# Bank_0_Bank_14.net
KiCad netlist of a schematic drawn in Altium Designer
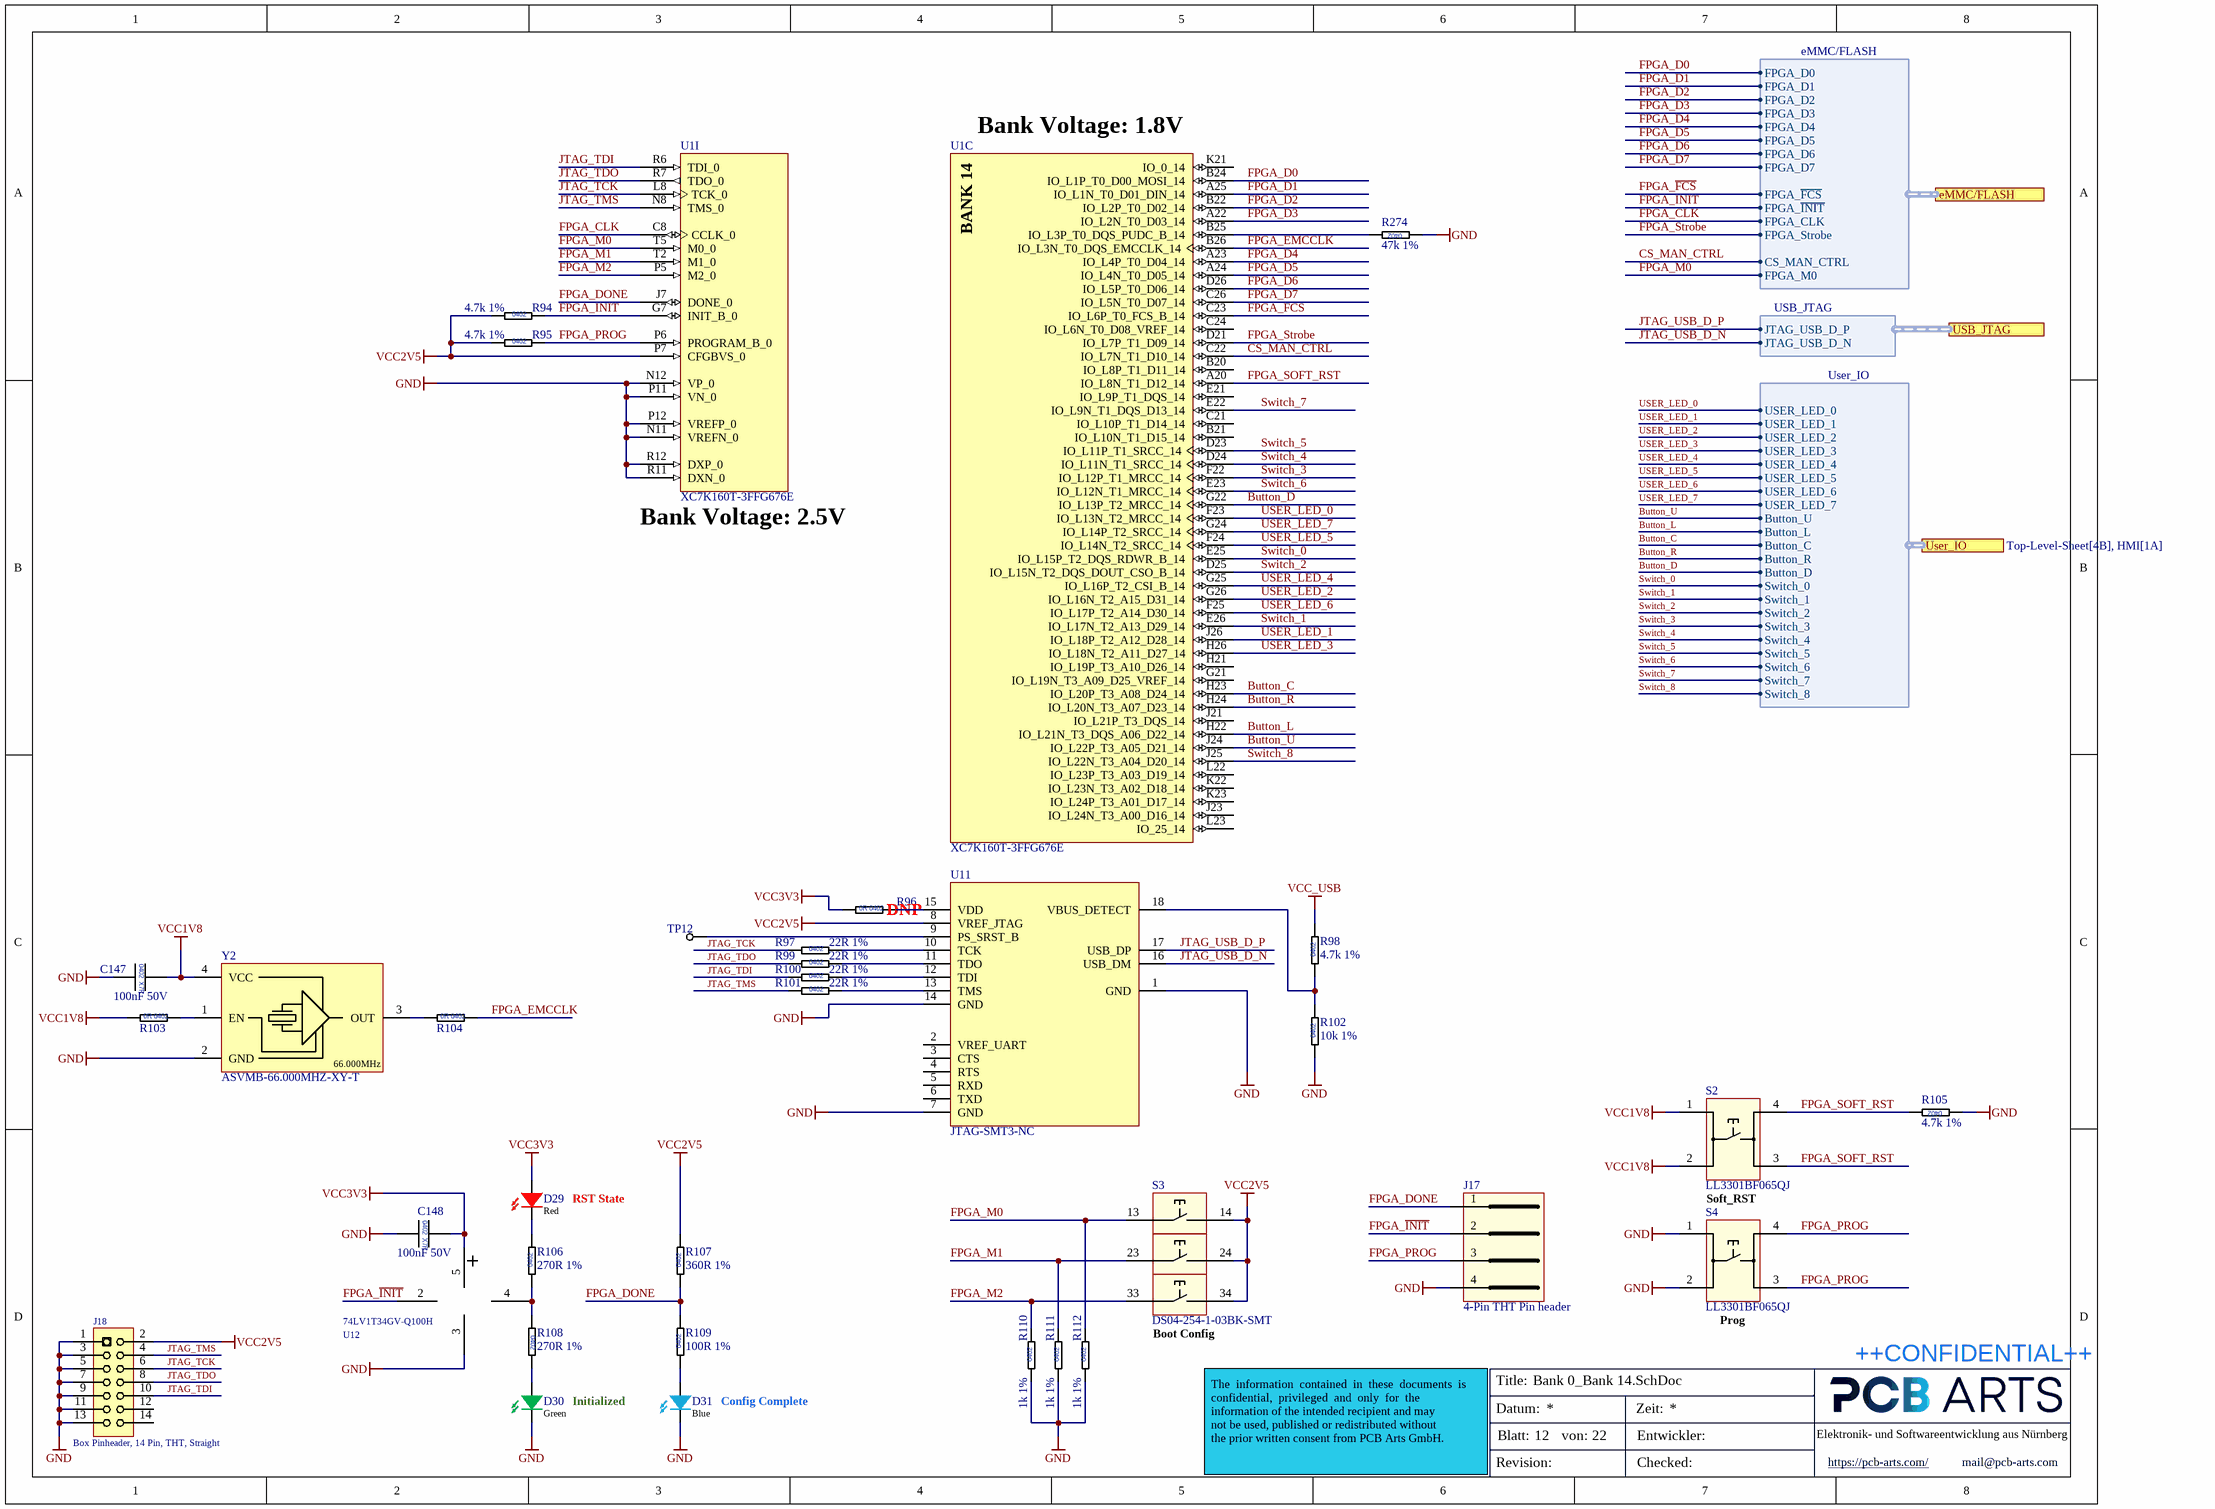
[diagram p0: Bank 0_Bank 14.SchDoc]

(export (version "E")
  (design (tool "Eeschema 10.0.6"))
  (components
    (comp (ref "C147")
      (value "100nF 50V")
      (footprint "Cap:CAP_0402_L")
      (description "Multilayer Ceramic Capacitors MLCC - SMD/SMT 0402 50VDC")
      (libsource (lib "Cap") (part "CAP_0402_100nF_50V"))
    )
    (comp (ref "C148")
      (value "100nF 50V")
      (footprint "Cap:CAP_0402_L")
      (description "Multilayer Ceramic Capacitors MLCC - SMD/SMT 0402 50VDC")
      (libsource (lib "Cap") (part "CAP_0402_100nF_50V"))
    )
    (comp (ref "D29")
      (value "LTST-S270KRKT")
      (footprint "Active:LED-0603 Sideview")
      (description "RED  0603 Light Emitting Diode")
      (fields (field (name "COLOR") "Red"))
      (libsource (lib "Active") (part "LED 0603 Red Sideview"))
    )
    (comp (ref "D30")
      (value "LTST-S270KGKT")
      (footprint "Active:LED-0603 Sideview")
      (description "GREEN  0603 Light Emitting Diode")
      (fields (field (name "COLOR") "Green"))
      (libsource (lib "Active") (part "LED 0603 Green Sideview"))
    )
    (comp (ref "D31")
      (value "LTST-S270TBKT")
      (footprint "Active:LED-0603 Sideview")
      (description "BLUE  0603 Light Emitting Diode")
      (fields (field (name "COLOR") "Blue"))
      (libsource (lib "Active") (part "LED 0603 Blue Sideview"))
    )
    (comp (ref "J17")
      (value "4-Pin THT Pin header")
      (footprint "Conn:61300411121")
      (description "WR-PHD 2.54mm 4Pin THT Header")
      (libsource (lib "Conn") (part "61300411121_WR-PHD 2.54mm 4Pin THT Header"))
    )
    (comp (ref "J18")
      (value "Box Pinheader, 14 Pin, THT, Straight")
      (footprint "Conn:87832-1420")
      (description "Box Pin header THT 2.00mm 14Pol Straight")
      (libsource (lib "Conn") (part "87832-1420_Box Pin header THT 2.00mm Box 14Pol Straight"))
    )
    (comp (ref "R94")
      (value "4.7k 1%")
      (footprint "Res:RES_0402_L")
      (description "Thick Film Resistors - SMD 4.7kOhm 1%")
      (libsource (lib "Res") (part "RES_0402_4.7k_1%"))
    )
    (comp (ref "R95")
      (value "4.7k 1%")
      (footprint "Res:RES_0402_L")
      (description "Thick Film Resistors - SMD 4.7kOhm 1%")
      (libsource (lib "Res") (part "RES_0402_4.7k_1%"))
    )
    (comp (ref "R96")
      (value "0R Jumper")
      (footprint "Res:RES_0402_L")
      (description "Thick Film Resistors - SMD 0Ohm")
      (libsource (lib "Res") (part "RES_0402_0R Jumper"))
    )
    (comp (ref "R97")
      (value "22R 1%")
      (footprint "Res:RES_0402_L")
      (description "Thick Film Resistors - SMD 22Ohm 1%")
      (libsource (lib "Res") (part "RES_0402_22R_1%"))
    )
    (comp (ref "R98")
      (value "4.7k 1%")
      (footprint "Res:RES_0402_L")
      (description "Thick Film Resistors - SMD 4.7kOhm 1%")
      (libsource (lib "Res") (part "RES_0402_4.7k_1%"))
    )
    (comp (ref "R99")
      (value "22R 1%")
      (footprint "Res:RES_0402_L")
      (description "Thick Film Resistors - SMD 22Ohm 1%")
      (libsource (lib "Res") (part "RES_0402_22R_1%"))
    )
    (comp (ref "R100")
      (value "22R 1%")
      (footprint "Res:RES_0402_L")
      (description "Thick Film Resistors - SMD 22Ohm 1%")
      (libsource (lib "Res") (part "RES_0402_22R_1%"))
    )
    (comp (ref "R101")
      (value "22R 1%")
      (footprint "Res:RES_0402_L")
      (description "Thick Film Resistors - SMD 22Ohm 1%")
      (libsource (lib "Res") (part "RES_0402_22R_1%"))
    )
    (comp (ref "R102")
      (value "10k 1%")
      (footprint "Res:RES_0402_L")
      (description "Thick Film Resistors - SMD 10kOhm 1%")
      (libsource (lib "Res") (part "RES_0402_10k_1%"))
    )
    (comp (ref "R103")
      (value "0R Jumper")
      (footprint "Res:RES_0402_L")
      (description "Thick Film Resistors - SMD 0Ohm")
      (libsource (lib "Res") (part "RES_0402_0R Jumper"))
    )
    (comp (ref "R104")
      (value "0R Jumper")
      (footprint "Res:RES_0402_L")
      (description "Thick Film Resistors - SMD 0Ohm")
      (libsource (lib "Res") (part "RES_0402_0R Jumper"))
    )
    (comp (ref "R105")
      (value "4.7k 1%")
      (footprint "Res:RES_0402_L")
      (description "Thick Film Resistors - SMD 4.7kOhm 1%")
      (libsource (lib "Res") (part "RES_0402_4.7k_1%"))
    )
    (comp (ref "R106")
      (value "270R 1%")
      (footprint "Res:RES_0402_L")
      (description "Thick Film Resistors - SMD 270Ohm 1%")
      (libsource (lib "Res") (part "RES_0402_270R 1%"))
    )
    (comp (ref "R107")
      (value "360R 1%")
      (footprint "Res:RES_0402_L")
      (description "Thick Film Resistors - SMD 360Ohm 1%")
      (libsource (lib "Res") (part "RES_0402_360R_1%"))
    )
    (comp (ref "R108")
      (value "270R 1%")
      (footprint "Res:RES_0402_L")
      (description "Thick Film Resistors - SMD 270Ohm 1%")
      (libsource (lib "Res") (part "RES_0402_270R 1%"))
    )
    (comp (ref "R109")
      (value "100R 1%")
      (footprint "Res:RES_0402_L")
      (description "Thick Film Resistors - SMD 100Ohm 1%")
      (libsource (lib "Res") (part "RES_0402_100R_1%"))
    )
    (comp (ref "R110")
      (value "1k 1%")
      (footprint "Res:RES_0402_L")
      (description "Thick Film Resistors - SMD 1kOhm 1%")
      (libsource (lib "Res") (part "RES_0402_1k_1%"))
    )
    (comp (ref "R111")
      (value "1k 1%")
      (footprint "Res:RES_0402_L")
      (description "Thick Film Resistors - SMD 1kOhm 1%")
      (libsource (lib "Res") (part "RES_0402_1k_1%"))
    )
    (comp (ref "R112")
      (value "1k 1%")
      (footprint "Res:RES_0402_L")
      (description "Thick Film Resistors - SMD 1kOhm 1%")
      (libsource (lib "Res") (part "RES_0402_1k_1%"))
    )
    (comp (ref "R274")
      (value "47k 1%")
      (footprint "Res:RES_0402_L")
      (description "Thick Film Resistors - SMD 47kOhm 1%")
      (libsource (lib "Res") (part "RES_0402_47k_1%"))
    )
    (comp (ref "S2")
      (value "LL3301BF065QJ")
      (footprint "Electro_Mech:LL3301BF065QJ")
      (description "SPST Top Actuated  Button, 65gf, SMD h: 9.8mm")
      (libsource (lib "Electro_Mech") (part "LL3301BF065QJ_SPST Top Actuated  Button, 65gf, SMD h{colon} 9.8mm"))
    )
    (comp (ref "S3")
      (value "DS04-254-1-03BK-SMT")
      (footprint "Electro_Mech:CUI DS04-254-SMT Series, 3 Pole")
      (description "SMD DIP Switch, 3 Pos, Slide actuator")
      (libsource (lib "Electro_Mech") (part "DS04-254-1-03BK-SMT"))
    )
    (comp (ref "S4")
      (value "LL3301BF065QJ")
      (footprint "Electro_Mech:LL3301BF065QJ")
      (description "SPST Top Actuated  Button, 65gf, SMD h: 9.8mm")
      (libsource (lib "Electro_Mech") (part "LL3301BF065QJ_SPST Top Actuated  Button, 65gf, SMD h{colon} 9.8mm"))
    )
    (comp (ref "TP12")
      (value "Testpoint")
      (footprint "Electro_mech:Testpoint 0.8mm")
      (description "Testpoint 0.8mm")
      (libsource (lib "Electro_Mech") (part "Testpoint 0.8mm"))
    )
    (comp (ref "U1")
      (value "XC7K160T-3FFG676E")
      (footprint "Digital:BGA100P2700X2700X317-676N")
      (description "Kintex-7 FPGA, 400 User I/Os, 8 GTX, 676-Ball BGA, Speed Grade 3, Extended Grade, Pb-Free")
      (libsource (lib "Digital") (part "XC7K160T-3FFG676E_Kintex-7 FPGA, 400 User I/Os, 8 GTX, FFG676"))
    )
    (comp (ref "U11")
      (value "JTAG-SMT3-NC")
      (footprint "Conn_Modules:JTAG-SMT3-NC")
      (description "Surface-mount JTAG Programming + UART Module")
      (libsource (lib "Conn_Modules") (part "JTAG-SMT3-NC_Surface-mount JTAG Programming + UART Module"))
    )
    (comp (ref "U12")
      (value "74LV1T34GV-Q100H")
      (footprint "Digital:SOT95P275X110-5N")
      (description "Single supply translating buffer")
      (libsource (lib "Digital") (part "74LV1T34GV-Q100H_Single supply translating buffe"))
    )
    (comp (ref "Y2")
      (value "ASVMB-66.000MHZ-XY-T")
      (footprint "Timer:ASVMB Series")
      (description "Clock-Memsoszillator 66.000MHz 1.8V 10ppm -40C +105C")
      (libsource (lib "Timer") (part "ASVMB-66.000MHZ-XY-T_Clock-Memsoszillator 66.000MHz 1.8V 10ppm -40C +105C"))
    )
  )
  (nets
    (net (code "4") (name "/Button_C") (class "Default")
      (node (ref "U1") (pin "H23") (pinfunction "IO_L20P_T3_A08_D24_14_H23") (pintype "bidirectional"))
    )
    (net (code "5") (name "/Button_D") (class "Default")
      (node (ref "U1") (pin "G22") (pinfunction "IO_L13P_T2_MRCC_14_G22") (pintype "bidirectional"))
    )
    (net (code "6") (name "/Button_L") (class "Default")
      (node (ref "U1") (pin "H22") (pinfunction "IO_L21N_T3_DQS_A06_D22_14_H22") (pintype "bidirectional"))
    )
    (net (code "7") (name "/Button_R") (class "Default")
      (node (ref "U1") (pin "H24") (pinfunction "IO_L20N_T3_A07_D23_14_H24") (pintype "bidirectional"))
    )
    (net (code "8") (name "/Button_U") (class "Default")
      (node (ref "U1") (pin "J24") (pinfunction "IO_L22P_T3_A05_D21_14_J24") (pintype "bidirectional"))
    )
    (net (code "9") (name "/CS_MAN_CTRL") (class "Default")
      (node (ref "U1") (pin "C22") (pinfunction "IO_L7N_T1_D10_14_C22") (pintype "bidirectional"))
    )
    (net (code "10") (name "/FPGA_CLK") (class "Default")
      (node (ref "U1") (pin "C8") (pinfunction "CCLK_0_C8") (pintype "bidirectional"))
    )
    (net (code "11") (name "/FPGA_D0") (class "Default")
      (node (ref "U1") (pin "B24") (pinfunction "IO_L1P_T0_D00_MOSI_14_B24") (pintype "bidirectional"))
    )
    (net (code "12") (name "/FPGA_D1") (class "Default")
      (node (ref "U1") (pin "A25") (pinfunction "IO_L1N_T0_D01_DIN_14_A25") (pintype "bidirectional"))
    )
    (net (code "13") (name "/FPGA_D2") (class "Default")
      (node (ref "U1") (pin "B22") (pinfunction "IO_L2P_T0_D02_14_B22") (pintype "bidirectional"))
    )
    (net (code "14") (name "/FPGA_D3") (class "Default")
      (node (ref "U1") (pin "A22") (pinfunction "IO_L2N_T0_D03_14_A22") (pintype "bidirectional"))
    )
    (net (code "15") (name "/FPGA_D4") (class "Default")
      (node (ref "U1") (pin "A23") (pinfunction "IO_L4P_T0_D04_14_A23") (pintype "bidirectional"))
    )
    (net (code "16") (name "/FPGA_D5") (class "Default")
      (node (ref "U1") (pin "A24") (pinfunction "IO_L4N_T0_D05_14_A24") (pintype "bidirectional"))
    )
    (net (code "17") (name "/FPGA_D6") (class "Default")
      (node (ref "U1") (pin "D26") (pinfunction "IO_L5P_T0_D06_14_D26") (pintype "bidirectional"))
    )
    (net (code "18") (name "/FPGA_D7") (class "Default")
      (node (ref "U1") (pin "C26") (pinfunction "IO_L5N_T0_D07_14_C26") (pintype "bidirectional"))
    )
    (net (code "19") (name "/FPGA_DONE") (class "Default")
      (node (ref "J17") (pin "1") (pinfunction "1_1") (pintype "passive"))
      (node (ref "R107") (pin "1") (pinfunction "1_1") (pintype "passive"))
      (node (ref "R109") (pin "2") (pinfunction "2_2") (pintype "passive"))
      (node (ref "U1") (pin "J7") (pinfunction "DONE_0_J7") (pintype "bidirectional"))
    )
    (net (code "20") (name "/FPGA_EMCCLK") (class "Default")
      (node (ref "R104") (pin "2") (pinfunction "2_2") (pintype "passive"))
      (node (ref "U1") (pin "B26") (pinfunction "IO_L3N_T0_DQS_EMCCLK_14_B26") (pintype "bidirectional"))
    )
    (net (code "21") (name "/FPGA_M0") (class "Default")
      (node (ref "R112") (pin "2") (pinfunction "2_2") (pintype "passive"))
      (node (ref "S3") (pin "13") (pinfunction "13_13") (pintype "passive"))
      (node (ref "U1") (pin "T5") (pinfunction "M0_0_T5") (pintype "input"))
    )
    (net (code "22") (name "/FPGA_M1") (class "Default")
      (node (ref "R111") (pin "2") (pinfunction "2_2") (pintype "passive"))
      (node (ref "S3") (pin "23") (pinfunction "23_23") (pintype "passive"))
      (node (ref "U1") (pin "T2") (pinfunction "M1_0_T2") (pintype "input"))
    )
    (net (code "23") (name "/FPGA_M2") (class "Default")
      (node (ref "R110") (pin "2") (pinfunction "2_2") (pintype "passive"))
      (node (ref "S3") (pin "33") (pinfunction "33_33") (pintype "passive"))
      (node (ref "U1") (pin "P5") (pinfunction "M2_0_P5") (pintype "input"))
    )
    (net (code "24") (name "/FPGA_PROG") (class "Default")
      (node (ref "J17") (pin "3") (pinfunction "3_3") (pintype "passive"))
      (node (ref "R95") (pin "2") (pinfunction "2_2") (pintype "passive"))
      (node (ref "S4") (pin "3") (pinfunction "3_3") (pintype "passive"))
      (node (ref "S4") (pin "4") (pinfunction "4_4") (pintype "passive"))
      (node (ref "U1") (pin "P6") (pinfunction "PROGRAM_B_0_P6") (pintype "input"))
    )
    (net (code "25") (name "/FPGA_SOFT_RST") (class "Default")
      (node (ref "R105") (pin "2") (pinfunction "2_2") (pintype "passive"))
      (node (ref "S2") (pin "3") (pinfunction "3_3") (pintype "passive"))
      (node (ref "S2") (pin "4") (pinfunction "4_4") (pintype "passive"))
      (node (ref "U1") (pin "A20") (pinfunction "IO_L8N_T1_D12_14_A20") (pintype "bidirectional"))
    )
    (net (code "26") (name "/FPGA_Strobe") (class "Default")
      (node (ref "U1") (pin "D21") (pinfunction "IO_L7P_T1_D09_14_D21") (pintype "bidirectional"))
    )
    (net (code "27") (name "/FPGA_~{FCS}") (class "Default")
      (node (ref "U1") (pin "C23") (pinfunction "IO_L6P_T0_FCS_B_14_C23") (pintype "bidirectional"))
    )
    (net (code "28") (name "/FPGA_~{INIT}") (class "Default")
      (node (ref "J17") (pin "2") (pinfunction "2_2") (pintype "passive"))
      (node (ref "R94") (pin "2") (pinfunction "2_2") (pintype "passive"))
      (node (ref "U1") (pin "G7") (pinfunction "INIT_B_0_G7") (pintype "bidirectional"))
      (node (ref "U12") (pin "2") (pinfunction "A_2") (pintype "passive"))
    )
    (net (code "29") (name "/JTAG_TCK") (class "Default")
      (node (ref "J18") (pin "6") (pinfunction "6_6") (pintype "passive"))
      (node (ref "R97") (pin "1") (pinfunction "1_1") (pintype "passive"))
      (node (ref "U1") (pin "L8") (pinfunction "TCK_0_L8") (pintype "input"))
    )
    (net (code "30") (name "/JTAG_TDI") (class "Default")
      (node (ref "J18") (pin "10") (pinfunction "10_10") (pintype "passive"))
      (node (ref "R100") (pin "1") (pinfunction "1_1") (pintype "passive"))
      (node (ref "U1") (pin "R6") (pinfunction "TDI_0_R6") (pintype "input"))
    )
    (net (code "31") (name "/JTAG_TDO") (class "Default")
      (node (ref "J18") (pin "8") (pinfunction "8_8") (pintype "passive"))
      (node (ref "R99") (pin "1") (pinfunction "1_1") (pintype "passive"))
      (node (ref "U1") (pin "R7") (pinfunction "TDO_0_R7") (pintype "output"))
    )
    (net (code "32") (name "/JTAG_TMS") (class "Default")
      (node (ref "J18") (pin "4") (pinfunction "4_4") (pintype "passive"))
      (node (ref "R101") (pin "1") (pinfunction "1_1") (pintype "passive"))
      (node (ref "U1") (pin "N8") (pinfunction "TMS_0_N8") (pintype "input"))
    )
    (net (code "33") (name "/JTAG_USB_D_N") (class "Default")
      (node (ref "U11") (pin "16") (pinfunction "USB_DM_16") (pintype "passive"))
    )
    (net (code "34") (name "/JTAG_USB_D_P") (class "Default")
      (node (ref "U11") (pin "17") (pinfunction "USB_DP_17") (pintype "passive"))
    )
    (net (code "35") (name "/Switch_0") (class "Default")
      (node (ref "U1") (pin "E25") (pinfunction "IO_L15P_T2_DQS_RDWR_B_14_E25") (pintype "bidirectional"))
    )
    (net (code "36") (name "/Switch_1") (class "Default")
      (node (ref "U1") (pin "E26") (pinfunction "IO_L17N_T2_A13_D29_14_E26") (pintype "bidirectional"))
    )
    (net (code "37") (name "/Switch_2") (class "Default")
      (node (ref "U1") (pin "D25") (pinfunction "IO_L15N_T2_DQS_DOUT_CSO_B_14_D25") (pintype "bidirectional"))
    )
    (net (code "38") (name "/Switch_3") (class "Default")
      (node (ref "U1") (pin "F22") (pinfunction "IO_L12P_T1_MRCC_14_F22") (pintype "bidirectional"))
    )
    (net (code "39") (name "/Switch_4") (class "Default")
      (node (ref "U1") (pin "D24") (pinfunction "IO_L11N_T1_SRCC_14_D24") (pintype "bidirectional"))
    )
    (net (code "40") (name "/Switch_5") (class "Default")
      (node (ref "U1") (pin "D23") (pinfunction "IO_L11P_T1_SRCC_14_D23") (pintype "bidirectional"))
    )
    (net (code "41") (name "/Switch_6") (class "Default")
      (node (ref "U1") (pin "E23") (pinfunction "IO_L12N_T1_MRCC_14_E23") (pintype "bidirectional"))
    )
    (net (code "42") (name "/Switch_7") (class "Default")
      (node (ref "U1") (pin "E22") (pinfunction "IO_L9N_T1_DQS_D13_14_E22") (pintype "bidirectional"))
    )
    (net (code "43") (name "/Switch_8") (class "Default")
      (node (ref "U1") (pin "J25") (pinfunction "IO_L22N_T3_A04_D20_14_J25") (pintype "bidirectional"))
    )
    (net (code "44") (name "/USER_LED_0") (class "Default")
      (node (ref "U1") (pin "F23") (pinfunction "IO_L13N_T2_MRCC_14_F23") (pintype "bidirectional"))
    )
    (net (code "45") (name "/USER_LED_1") (class "Default")
      (node (ref "U1") (pin "J26") (pinfunction "IO_L18P_T2_A12_D28_14_J26") (pintype "bidirectional"))
    )
    (net (code "46") (name "/USER_LED_2") (class "Default")
      (node (ref "U1") (pin "G26") (pinfunction "IO_L16N_T2_A15_D31_14_G26") (pintype "bidirectional"))
    )
    (net (code "47") (name "/USER_LED_3") (class "Default")
      (node (ref "U1") (pin "H26") (pinfunction "IO_L18N_T2_A11_D27_14_H26") (pintype "bidirectional"))
    )
    (net (code "48") (name "/USER_LED_4") (class "Default")
      (node (ref "U1") (pin "G25") (pinfunction "IO_L16P_T2_CSI_B_14_G25") (pintype "bidirectional"))
    )
    (net (code "49") (name "/USER_LED_5") (class "Default")
      (node (ref "U1") (pin "F24") (pinfunction "IO_L14N_T2_SRCC_14_F24") (pintype "bidirectional"))
    )
    (net (code "50") (name "/USER_LED_6") (class "Default")
      (node (ref "U1") (pin "F25") (pinfunction "IO_L17P_T2_A14_D30_14_F25") (pintype "bidirectional"))
    )
    (net (code "51") (name "/USER_LED_7") (class "Default")
      (node (ref "U1") (pin "G24") (pinfunction "IO_L14P_T2_SRCC_14_G24") (pintype "bidirectional"))
    )
    (net (code "55") (name "GND") (class "Default")
      (node (ref "C147") (pin "2") (pinfunction "2_2") (pintype "passive"))
      (node (ref "C148") (pin "2") (pinfunction "2_2") (pintype "passive"))
      (node (ref "D30") (pin "1") (pinfunction "1_1") (pintype "passive"))
      (node (ref "D31") (pin "1") (pinfunction "1_1") (pintype "passive"))
      (node (ref "J17") (pin "4") (pinfunction "4_4") (pintype "passive"))
      (node (ref "J18") (pin "1") (pinfunction "1_1") (pintype "passive"))
      (node (ref "J18") (pin "11") (pinfunction "11_11") (pintype "passive"))
      (node (ref "J18") (pin "13") (pinfunction "13_13") (pintype "passive"))
      (node (ref "J18") (pin "3") (pinfunction "3_3") (pintype "passive"))
      (node (ref "J18") (pin "5") (pinfunction "5_5") (pintype "passive"))
      (node (ref "J18") (pin "7") (pinfunction "7_7") (pintype "passive"))
      (node (ref "J18") (pin "9") (pinfunction "9_9") (pintype "passive"))
      (node (ref "R102") (pin "1") (pinfunction "1_1") (pintype "passive"))
      (node (ref "R105") (pin "1") (pinfunction "1_1") (pintype "passive"))
      (node (ref "R110") (pin "1") (pinfunction "1_1") (pintype "passive"))
      (node (ref "R111") (pin "1") (pinfunction "1_1") (pintype "passive"))
      (node (ref "R112") (pin "1") (pinfunction "1_1") (pintype "passive"))
      (node (ref "R274") (pin "1") (pinfunction "1_1") (pintype "passive"))
      (node (ref "S4") (pin "1") (pinfunction "1_1") (pintype "passive"))
      (node (ref "S4") (pin "2") (pinfunction "2_2") (pintype "passive"))
      (node (ref "U1") (pin "N11") (pinfunction "VREFN_0_N11") (pintype "input"))
      (node (ref "U1") (pin "N12") (pinfunction "VP_0_N12") (pintype "input"))
      (node (ref "U1") (pin "P11") (pinfunction "VN_0_P11") (pintype "input"))
      (node (ref "U1") (pin "P12") (pinfunction "VREFP_0_P12") (pintype "input"))
      (node (ref "U1") (pin "R11") (pinfunction "DXN_0_R11") (pintype "input"))
      (node (ref "U1") (pin "R12") (pinfunction "DXP_0_R12") (pintype "input"))
      (node (ref "U11") (pin "1") (pinfunction "GND_1") (pintype "passive"))
      (node (ref "U11") (pin "14") (pinfunction "GND_14") (pintype "passive"))
      (node (ref "U11") (pin "7") (pinfunction "GND_7") (pintype "passive"))
      (node (ref "U12") (pin "3") (pinfunction "GND_3") (pintype "passive"))
      (node (ref "Y2") (pin "2") (pinfunction "GND_2") (pintype "passive"))
    )
    (net (code "56") (name "Net-(D29-Pad1)") (class "Default")
      (node (ref "D29") (pin "1") (pinfunction "1_1") (pintype "passive"))
      (node (ref "R106") (pin "2") (pinfunction "2_2") (pintype "passive"))
    )
    (net (code "57") (name "Net-(D30-Pad2)") (class "Default")
      (node (ref "D30") (pin "2") (pinfunction "2_2") (pintype "passive"))
      (node (ref "R108") (pin "2") (pinfunction "2_2") (pintype "passive"))
    )
    (net (code "58") (name "Net-(D31-Pad2)") (class "Default")
      (node (ref "D31") (pin "2") (pinfunction "2_2") (pintype "passive"))
      (node (ref "R109") (pin "1") (pinfunction "1_1") (pintype "passive"))
    )
    (net (code "59") (name "Net-(TP12-GND)") (class "Default")
      (node (ref "TP12") (pin "1") (pinfunction "GND_1") (pintype "passive"))
      (node (ref "U11") (pin "9") (pinfunction "PS_SRST_B_9") (pintype "passive"))
    )
    (net (code "60") (name "Net-(U1C-IO_L3P_T0_DQS_PUDC_B_14)") (class "Default")
      (node (ref "R274") (pin "2") (pinfunction "2_2") (pintype "passive"))
      (node (ref "U1") (pin "B25") (pinfunction "IO_L3P_T0_DQS_PUDC_B_14_B25") (pintype "bidirectional"))
    )
    (net (code "61") (name "Net-(U11-TCK)") (class "Default")
      (node (ref "R97") (pin "2") (pinfunction "2_2") (pintype "passive"))
      (node (ref "U11") (pin "10") (pinfunction "TCK_10") (pintype "passive"))
    )
    (net (code "62") (name "Net-(U11-TDI)") (class "Default")
      (node (ref "R100") (pin "2") (pinfunction "2_2") (pintype "passive"))
      (node (ref "U11") (pin "12") (pinfunction "TDI_12") (pintype "passive"))
    )
    (net (code "63") (name "Net-(U11-TDO)") (class "Default")
      (node (ref "R99") (pin "2") (pinfunction "2_2") (pintype "passive"))
      (node (ref "U11") (pin "11") (pinfunction "TDO_11") (pintype "passive"))
    )
    (net (code "64") (name "Net-(U11-TMS)") (class "Default")
      (node (ref "R101") (pin "2") (pinfunction "2_2") (pintype "passive"))
      (node (ref "U11") (pin "13") (pinfunction "TMS_13") (pintype "passive"))
    )
    (net (code "65") (name "Net-(U11-VBUS_DETECT)") (class "Default")
      (node (ref "R102") (pin "2") (pinfunction "2_2") (pintype "passive"))
      (node (ref "R98") (pin "1") (pinfunction "1_1") (pintype "passive"))
      (node (ref "U11") (pin "18") (pinfunction "VBUS_DETECT_18") (pintype "passive"))
    )
    (net (code "66") (name "Net-(U11-VDD)") (class "Default")
      (node (ref "R96") (pin "2") (pinfunction "2_2") (pintype "passive"))
      (node (ref "U11") (pin "15") (pinfunction "VDD_15") (pintype "passive"))
    )
    (net (code "67") (name "Net-(U12-Y)") (class "Default")
      (node (ref "R106") (pin "1") (pinfunction "1_1") (pintype "passive"))
      (node (ref "R108") (pin "1") (pinfunction "1_1") (pintype "passive"))
      (node (ref "U12") (pin "4") (pinfunction "Y_4") (pintype "passive"))
    )
    (net (code "68") (name "Net-(Y2-EN)") (class "Default")
      (node (ref "R103") (pin "2") (pinfunction "2_2") (pintype "passive"))
      (node (ref "Y2") (pin "1") (pinfunction "EN_1") (pintype "passive"))
    )
    (net (code "69") (name "Net-(Y2-OUT)") (class "Default")
      (node (ref "R104") (pin "1") (pinfunction "1_1") (pintype "passive"))
      (node (ref "Y2") (pin "3") (pinfunction "OUT_3") (pintype "passive"))
    )
    (net (code "70") (name "VCC1V8") (class "Default")
      (node (ref "C147") (pin "1") (pinfunction "1_1") (pintype "passive"))
      (node (ref "R103") (pin "1") (pinfunction "1_1") (pintype "passive"))
      (node (ref "S2") (pin "1") (pinfunction "1_1") (pintype "passive"))
      (node (ref "S2") (pin "2") (pinfunction "2_2") (pintype "passive"))
      (node (ref "Y2") (pin "4") (pinfunction "VCC_4") (pintype "passive"))
    )
    (net (code "71") (name "VCC2V5") (class "Default")
      (node (ref "J18") (pin "2") (pinfunction "2_2") (pintype "passive"))
      (node (ref "R107") (pin "2") (pinfunction "2_2") (pintype "passive"))
      (node (ref "R94") (pin "1") (pinfunction "1_1") (pintype "passive"))
      (node (ref "R95") (pin "1") (pinfunction "1_1") (pintype "passive"))
      (node (ref "S3") (pin "14") (pinfunction "14_14") (pintype "passive"))
      (node (ref "S3") (pin "24") (pinfunction "24_24") (pintype "passive"))
      (node (ref "S3") (pin "34") (pinfunction "34_34") (pintype "passive"))
      (node (ref "U1") (pin "P7") (pinfunction "CFGBVS_0_P7") (pintype "input"))
      (node (ref "U11") (pin "8") (pinfunction "VREF_JTAG_8") (pintype "passive"))
    )
    (net (code "72") (name "VCC3V3") (class "Default")
      (node (ref "C148") (pin "1") (pinfunction "1_1") (pintype "passive"))
      (node (ref "D29") (pin "2") (pinfunction "2_2") (pintype "passive"))
      (node (ref "R96") (pin "1") (pinfunction "1_1") (pintype "passive"))
      (node (ref "U12") (pin "5") (pinfunction "VCC_5") (pintype "passive"))
    )
    (net (code "73") (name "VCC_USB") (class "Default")
      (node (ref "R98") (pin "2") (pinfunction "2_2") (pintype "passive"))
    )
    (net (code "74") (name "unconnected-(J18-Pad12)") (class "Default")
      (node (ref "J18") (pin "12") (pinfunction "12_12") (pintype "passive"))
    )
    (net (code "75") (name "unconnected-(J18-Pad14)") (class "Default")
      (node (ref "J18") (pin "14") (pinfunction "14_14") (pintype "passive"))
    )
    (net (code "76") (name "unconnected-(U1C-IO_0_14-PadK21)") (class "Default")
      (node (ref "U1") (pin "K21") (pinfunction "IO_0_14_K21") (pintype "bidirectional"))
    )
    (net (code "77") (name "unconnected-(U1C-IO_25_14-PadL23)") (class "Default")
      (node (ref "U1") (pin "L23") (pinfunction "IO_25_14_L23") (pintype "bidirectional"))
    )
    (net (code "78") (name "unconnected-(U1C-IO_L6N_T0_D08_VREF_14-PadC24)") (class "Default")
      (node (ref "U1") (pin "C24") (pinfunction "IO_L6N_T0_D08_VREF_14_C24") (pintype "bidirectional"))
    )
    (net (code "79") (name "unconnected-(U1C-IO_L8P_T1_D11_14-PadB20)") (class "Default")
      (node (ref "U1") (pin "B20") (pinfunction "IO_L8P_T1_D11_14_B20") (pintype "bidirectional"))
    )
    (net (code "80") (name "unconnected-(U1C-IO_L9P_T1_DQS_14-PadE21)") (class "Default")
      (node (ref "U1") (pin "E21") (pinfunction "IO_L9P_T1_DQS_14_E21") (pintype "bidirectional"))
    )
    (net (code "81") (name "unconnected-(U1C-IO_L10N_T1_D15_14-PadB21)") (class "Default")
      (node (ref "U1") (pin "B21") (pinfunction "IO_L10N_T1_D15_14_B21") (pintype "bidirectional"))
    )
    (net (code "82") (name "unconnected-(U1C-IO_L10P_T1_D14_14-PadC21)") (class "Default")
      (node (ref "U1") (pin "C21") (pinfunction "IO_L10P_T1_D14_14_C21") (pintype "bidirectional"))
    )
    (net (code "83") (name "unconnected-(U1C-IO_L19N_T3_A09_D25_VREF_14-PadG21)") (class "Default")
      (node (ref "U1") (pin "G21") (pinfunction "IO_L19N_T3_A09_D25_VREF_14_G21") (pintype "bidirectional"))
    )
    (net (code "84") (name "unconnected-(U1C-IO_L19P_T3_A10_D26_14-PadH21)") (class "Default")
      (node (ref "U1") (pin "H21") (pinfunction "IO_L19P_T3_A10_D26_14_H21") (pintype "bidirectional"))
    )
    (net (code "85") (name "unconnected-(U1C-IO_L21P_T3_DQS_14-PadJ21)") (class "Default")
      (node (ref "U1") (pin "J21") (pinfunction "IO_L21P_T3_DQS_14_J21") (pintype "bidirectional"))
    )
    (net (code "86") (name "unconnected-(U1C-IO_L23N_T3_A02_D18_14-PadK22)") (class "Default")
      (node (ref "U1") (pin "K22") (pinfunction "IO_L23N_T3_A02_D18_14_K22") (pintype "bidirectional"))
    )
    (net (code "87") (name "unconnected-(U1C-IO_L23P_T3_A03_D19_14-PadL22)") (class "Default")
      (node (ref "U1") (pin "L22") (pinfunction "IO_L23P_T3_A03_D19_14_L22") (pintype "bidirectional"))
    )
    (net (code "88") (name "unconnected-(U1C-IO_L24N_T3_A00_D16_14-PadJ23)") (class "Default")
      (node (ref "U1") (pin "J23") (pinfunction "IO_L24N_T3_A00_D16_14_J23") (pintype "bidirectional"))
    )
    (net (code "89") (name "unconnected-(U1C-IO_L24P_T3_A01_D17_14-PadK23)") (class "Default")
      (node (ref "U1") (pin "K23") (pinfunction "IO_L24P_T3_A01_D17_14_K23") (pintype "bidirectional"))
    )
    (net (code "90") (name "unconnected-(U11-CTS-Pad3)") (class "Default")
      (node (ref "U11") (pin "3") (pinfunction "CTS_3") (pintype "passive"))
    )
    (net (code "91") (name "unconnected-(U11-RTS-Pad4)") (class "Default")
      (node (ref "U11") (pin "4") (pinfunction "RTS_4") (pintype "passive"))
    )
    (net (code "92") (name "unconnected-(U11-RXD-Pad5)") (class "Default")
      (node (ref "U11") (pin "5") (pinfunction "RXD_5") (pintype "passive"))
    )
    (net (code "93") (name "unconnected-(U11-TXD-Pad6)") (class "Default")
      (node (ref "U11") (pin "6") (pinfunction "TXD_6") (pintype "passive"))
    )
    (net (code "94") (name "unconnected-(U11-VREF_UART-Pad2)") (class "Default")
      (node (ref "U11") (pin "2") (pinfunction "VREF_UART_2") (pintype "passive"))
    )
  )
)
